# CRUVI.net
KiCad netlist of a schematic drawn in Altium Designer
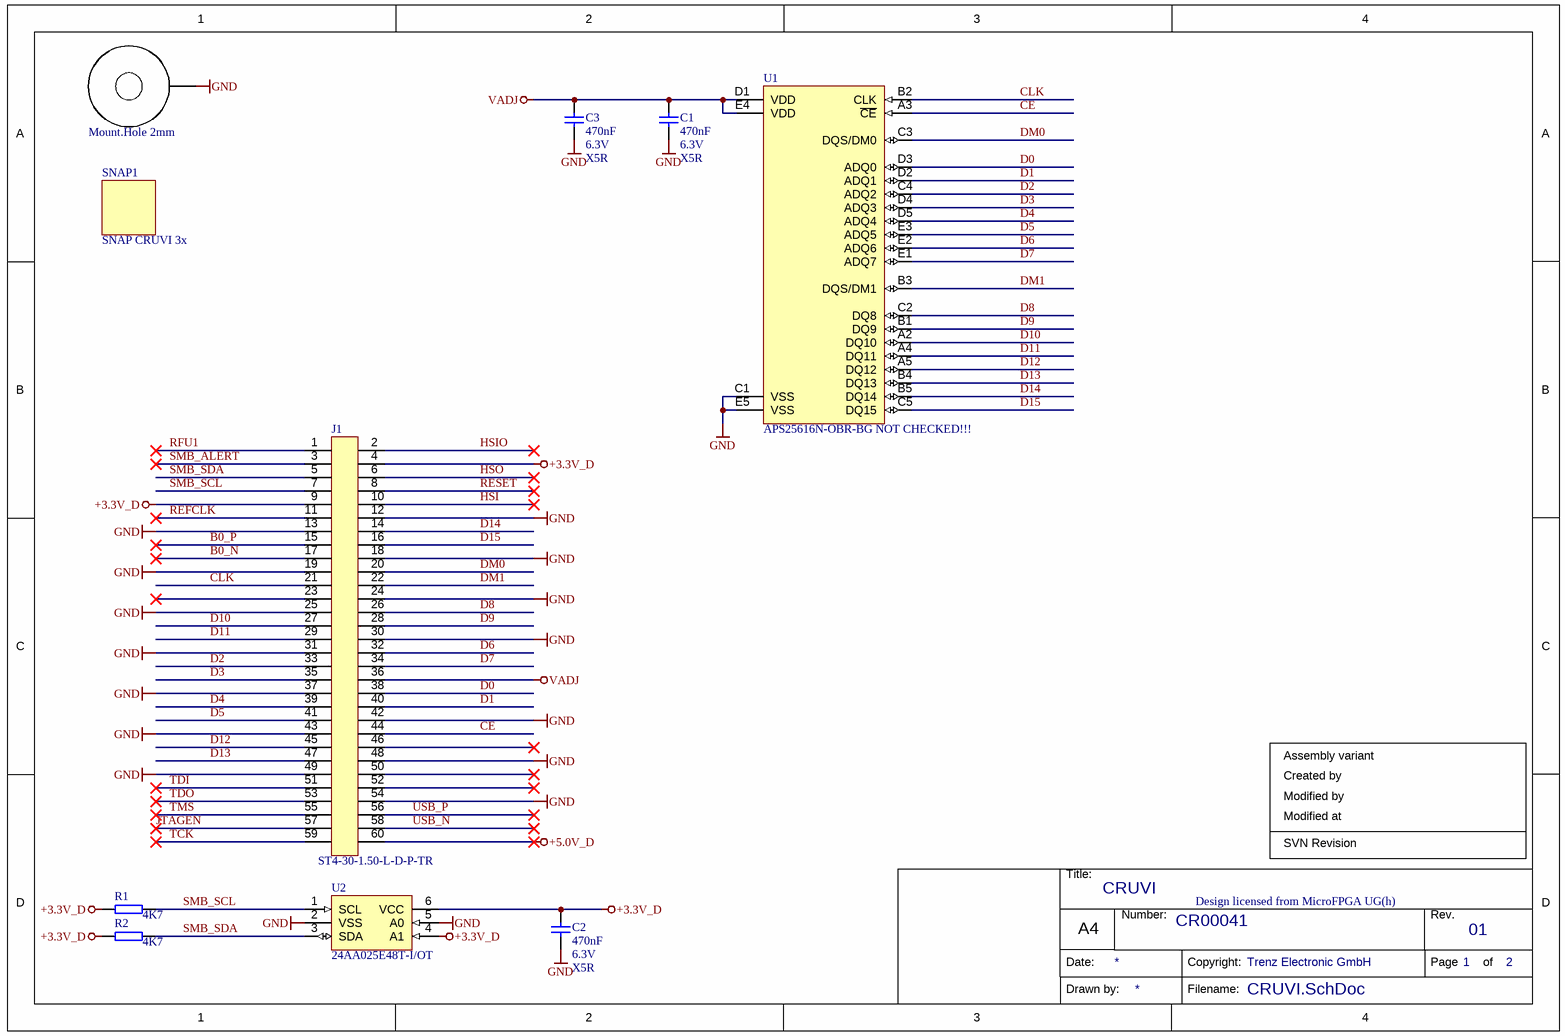
[diagram p0: CRUVI.SchDoc]

(export (version "E")
  (design (tool "Eeschema 10.0.6"))
  (components
    (comp (ref "C1")
      (value "470nF")
      (footprint "CAPC1005X55N_V")
      (description "KON 470nF 6,3V X5R SMD BF 1005 (0402)")
      (fields (field (name "VOLTAGE") "6.3V") (field (name "TECHNOLOGY") "X5R"))
      (libsource (lib "TE") (part "CAP-NP"))
    )
    (comp (ref "C2")
      (value "470nF")
      (footprint "CAPC1005X55N_V")
      (description "KON 470nF 6,3V X5R SMD BF 1005 (0402)")
      (fields (field (name "VOLTAGE") "6.3V") (field (name "TECHNOLOGY") "X5R"))
      (libsource (lib "TE") (part "CAP-NP"))
    )
    (comp (ref "C3")
      (value "470nF")
      (footprint "CAPC1005X55N_V")
      (description "KON 470nF 6,3V X5R SMD BF 1005 (0402)")
      (fields (field (name "VOLTAGE") "6.3V") (field (name "TECHNOLOGY") "X5R"))
      (libsource (lib "TE") (part "CAP-NP"))
    )
    (comp (ref "H3") (value "Mount.Hole 2mm") (footprint "MHole2_2mm") (libsource (lib "TE") (part "MHole")))
    (comp (ref "J1")
      (value "ST4-30-1.50-L-D-P-TR")
      (footprint "ST4-30-1_50-L-D")
      (libsource (lib "TE") (part "CON-60"))
    )
    (comp (ref "R1")
      (value "4K7")
      (footprint "RESC1005X40N_V")
      (description "WID SMD 4K7 1% 0,063W BF 1005 (0402)")
      (fields (field (name "TOLERANCE") "1%"))
      (libsource (lib "TE") (part "RES"))
    )
    (comp (ref "R2")
      (value "4K7")
      (footprint "RESC1005X40N_V")
      (description "WID SMD 4K7 1% 0,063W BF 1005 (0402)")
      (fields (field (name "TOLERANCE") "1%"))
      (libsource (lib "TE") (part "RES"))
    )
    (comp (ref "SNAP1")
      (value "SNAP CRUVI 3x")
      (footprint "CRUVI_3x_Snap")
      (description "SNAP for CRUVI 3x")
      (libsource (lib "TE") (part "DUMMY"))
    )
    (comp (ref "U1")
      (value "APS25616N-OBR-BG NOT CHECKED!!!")
      (footprint "BGA24C100P5X5_800X600X120N")
      (description "APS25616N-OBR-BG")
      (libsource (lib "TE") (part "APS25616N-OBR-BG"))
    )
    (comp (ref "U2")
      (value "24AA025E48T-I/OT")
      (footprint "SOT95P280X145-6N")
      (libsource (lib "TE") (part "24AA025E48"))
    )
  )
  (nets
    (net (code "1") (name "+3.3V_D") (class "Default")
      (node (ref "C2") (pin "1") (pinfunction "1_1") (pintype "passive"))
      (node (ref "J1") (pin "4") (pinfunction "4_4") (pintype "passive"))
      (node (ref "J1") (pin "9") (pinfunction "9_9") (pintype "passive"))
      (node (ref "R1") (pin "1") (pinfunction "1_1") (pintype "passive"))
      (node (ref "R2") (pin "1") (pinfunction "1_1") (pintype "passive"))
      (node (ref "U2") (pin "4") (pinfunction "A1_4") (pintype "input"))
      (node (ref "U2") (pin "6") (pinfunction "VCC_6") (pintype "power_in"))
    )
    (net (code "2") (name "+5.0V_D") (class "Default")
      (node (ref "J1") (pin "60") (pinfunction "60_60") (pintype "passive"))
    )
    (net (code "3") (name "/B0_N") (class "Default")
      (node (ref "J1") (pin "17") (pinfunction "17_17") (pintype "passive+no_connect"))
    )
    (net (code "4") (name "/B0_P") (class "Default")
      (node (ref "J1") (pin "15") (pinfunction "15_15") (pintype "passive+no_connect"))
    )
    (net (code "5") (name "/CE") (class "Default")
      (node (ref "J1") (pin "44") (pinfunction "44_44") (pintype "passive"))
      (node (ref "U1") (pin "A3") (pinfunction "~{CE}_A3") (pintype "input"))
    )
    (net (code "6") (name "/CLK") (class "Default")
      (node (ref "J1") (pin "21") (pinfunction "21_21") (pintype "passive"))
      (node (ref "U1") (pin "B2") (pinfunction "CLK_B2") (pintype "input"))
    )
    (net (code "7") (name "/D0") (class "Default")
      (node (ref "J1") (pin "38") (pinfunction "38_38") (pintype "passive"))
      (node (ref "U1") (pin "D3") (pinfunction "ADQ0_D3") (pintype "bidirectional"))
    )
    (net (code "8") (name "/D1") (class "Default")
      (node (ref "J1") (pin "40") (pinfunction "40_40") (pintype "passive"))
      (node (ref "U1") (pin "D2") (pinfunction "ADQ1_D2") (pintype "bidirectional"))
    )
    (net (code "9") (name "/D2") (class "Default")
      (node (ref "J1") (pin "33") (pinfunction "33_33") (pintype "passive"))
      (node (ref "U1") (pin "C4") (pinfunction "ADQ2_C4") (pintype "bidirectional"))
    )
    (net (code "10") (name "/D3") (class "Default")
      (node (ref "J1") (pin "35") (pinfunction "35_35") (pintype "passive"))
      (node (ref "U1") (pin "D4") (pinfunction "ADQ3_D4") (pintype "bidirectional"))
    )
    (net (code "11") (name "/D4") (class "Default")
      (node (ref "J1") (pin "39") (pinfunction "39_39") (pintype "passive"))
      (node (ref "U1") (pin "D5") (pinfunction "ADQ4_D5") (pintype "bidirectional"))
    )
    (net (code "12") (name "/D5") (class "Default")
      (node (ref "J1") (pin "41") (pinfunction "41_41") (pintype "passive"))
      (node (ref "U1") (pin "E3") (pinfunction "ADQ5_E3") (pintype "bidirectional"))
    )
    (net (code "13") (name "/D6") (class "Default")
      (node (ref "J1") (pin "32") (pinfunction "32_32") (pintype "passive"))
      (node (ref "U1") (pin "E2") (pinfunction "ADQ6_E2") (pintype "bidirectional"))
    )
    (net (code "14") (name "/D7") (class "Default")
      (node (ref "J1") (pin "34") (pinfunction "34_34") (pintype "passive"))
      (node (ref "U1") (pin "E1") (pinfunction "ADQ7_E1") (pintype "bidirectional"))
    )
    (net (code "15") (name "/D8") (class "Default")
      (node (ref "J1") (pin "26") (pinfunction "26_26") (pintype "passive"))
      (node (ref "U1") (pin "C2") (pinfunction "DQ8_C2") (pintype "bidirectional"))
    )
    (net (code "16") (name "/D9") (class "Default")
      (node (ref "J1") (pin "28") (pinfunction "28_28") (pintype "passive"))
      (node (ref "U1") (pin "B1") (pinfunction "DQ9_B1") (pintype "bidirectional"))
    )
    (net (code "17") (name "/D10") (class "Default")
      (node (ref "J1") (pin "27") (pinfunction "27_27") (pintype "passive"))
      (node (ref "U1") (pin "A2") (pinfunction "DQ10_A2") (pintype "bidirectional"))
    )
    (net (code "18") (name "/D11") (class "Default")
      (node (ref "J1") (pin "29") (pinfunction "29_29") (pintype "passive"))
      (node (ref "U1") (pin "A4") (pinfunction "DQ11_A4") (pintype "bidirectional"))
    )
    (net (code "19") (name "/D12") (class "Default")
      (node (ref "J1") (pin "45") (pinfunction "45_45") (pintype "passive"))
      (node (ref "U1") (pin "A5") (pinfunction "DQ12_A5") (pintype "bidirectional"))
    )
    (net (code "20") (name "/D13") (class "Default")
      (node (ref "J1") (pin "47") (pinfunction "47_47") (pintype "passive"))
      (node (ref "U1") (pin "B4") (pinfunction "DQ13_B4") (pintype "bidirectional"))
    )
    (net (code "21") (name "/D14") (class "Default")
      (node (ref "J1") (pin "14") (pinfunction "14_14") (pintype "passive"))
      (node (ref "U1") (pin "B5") (pinfunction "DQ14_B5") (pintype "bidirectional"))
    )
    (net (code "22") (name "/D15") (class "Default")
      (node (ref "J1") (pin "16") (pinfunction "16_16") (pintype "passive"))
      (node (ref "U1") (pin "C5") (pinfunction "DQ15_C5") (pintype "bidirectional"))
    )
    (net (code "23") (name "/DM0") (class "Default")
      (node (ref "J1") (pin "20") (pinfunction "20_20") (pintype "passive"))
      (node (ref "U1") (pin "C3") (pinfunction "DQS/DM0_C3") (pintype "bidirectional"))
    )
    (net (code "24") (name "/DM1") (class "Default")
      (node (ref "J1") (pin "22") (pinfunction "22_22") (pintype "passive"))
      (node (ref "U1") (pin "B3") (pinfunction "DQS/DM1_B3") (pintype "bidirectional"))
    )
    (net (code "25") (name "/HSI") (class "Default")
      (node (ref "J1") (pin "10") (pinfunction "10_10") (pintype "passive+no_connect"))
    )
    (net (code "26") (name "/HSIO") (class "Default")
      (node (ref "J1") (pin "2") (pinfunction "2_2") (pintype "passive+no_connect"))
    )
    (net (code "27") (name "/HSO") (class "Default")
      (node (ref "J1") (pin "6") (pinfunction "6_6") (pintype "passive+no_connect"))
    )
    (net (code "28") (name "/JTAGEN") (class "Default")
      (node (ref "J1") (pin "57") (pinfunction "57_57") (pintype "passive+no_connect"))
    )
    (net (code "29") (name "/REFCLK") (class "Default")
      (node (ref "J1") (pin "11") (pinfunction "11_11") (pintype "passive+no_connect"))
    )
    (net (code "30") (name "/RESET") (class "Default")
      (node (ref "J1") (pin "8") (pinfunction "8_8") (pintype "passive+no_connect"))
    )
    (net (code "31") (name "/RFU1") (class "Default")
      (node (ref "J1") (pin "1") (pinfunction "1_1") (pintype "passive+no_connect"))
    )
    (net (code "32") (name "/SMB_ALERT") (class "Default")
      (node (ref "J1") (pin "3") (pinfunction "3_3") (pintype "passive+no_connect"))
    )
    (net (code "33") (name "/SMB_SCL") (class "Default")
      (node (ref "J1") (pin "7") (pinfunction "7_7") (pintype "passive"))
      (node (ref "R1") (pin "2") (pinfunction "2_2") (pintype "passive"))
      (node (ref "U2") (pin "1") (pinfunction "SCL_1") (pintype "input"))
    )
    (net (code "34") (name "/SMB_SDA") (class "Default")
      (node (ref "J1") (pin "5") (pinfunction "5_5") (pintype "passive"))
      (node (ref "R2") (pin "2") (pinfunction "2_2") (pintype "passive"))
      (node (ref "U2") (pin "3") (pinfunction "SDA_3") (pintype "bidirectional"))
    )
    (net (code "35") (name "/TCK") (class "Default")
      (node (ref "J1") (pin "59") (pinfunction "59_59") (pintype "passive+no_connect"))
    )
    (net (code "36") (name "/TDI") (class "Default")
      (node (ref "J1") (pin "51") (pinfunction "51_51") (pintype "passive+no_connect"))
    )
    (net (code "37") (name "/TDO") (class "Default")
      (node (ref "J1") (pin "53") (pinfunction "53_53") (pintype "passive+no_connect"))
    )
    (net (code "38") (name "/TMS") (class "Default")
      (node (ref "J1") (pin "55") (pinfunction "55_55") (pintype "passive+no_connect"))
    )
    (net (code "39") (name "/USB_N") (class "Default")
      (node (ref "J1") (pin "58") (pinfunction "58_58") (pintype "passive+no_connect"))
    )
    (net (code "40") (name "/USB_P") (class "Default")
      (node (ref "J1") (pin "56") (pinfunction "56_56") (pintype "passive+no_connect"))
    )
    (net (code "41") (name "GND") (class "Default")
      (node (ref "C1") (pin "2") (pinfunction "2_2") (pintype "passive"))
      (node (ref "C2") (pin "2") (pinfunction "2_2") (pintype "passive"))
      (node (ref "C3") (pin "2") (pinfunction "2_2") (pintype "passive"))
      (node (ref "H3") (pin "1") (pinfunction "1_1") (pintype "passive"))
      (node (ref "J1") (pin "12") (pinfunction "12_12") (pintype "passive"))
      (node (ref "J1") (pin "13") (pinfunction "13_13") (pintype "passive"))
      (node (ref "J1") (pin "18") (pinfunction "18_18") (pintype "passive"))
      (node (ref "J1") (pin "19") (pinfunction "19_19") (pintype "passive"))
      (node (ref "J1") (pin "24") (pinfunction "24_24") (pintype "passive"))
      (node (ref "J1") (pin "25") (pinfunction "25_25") (pintype "passive"))
      (node (ref "J1") (pin "30") (pinfunction "30_30") (pintype "passive"))
      (node (ref "J1") (pin "31") (pinfunction "31_31") (pintype "passive"))
      (node (ref "J1") (pin "37") (pinfunction "37_37") (pintype "passive"))
      (node (ref "J1") (pin "42") (pinfunction "42_42") (pintype "passive"))
      (node (ref "J1") (pin "43") (pinfunction "43_43") (pintype "passive"))
      (node (ref "J1") (pin "48") (pinfunction "48_48") (pintype "passive"))
      (node (ref "J1") (pin "49") (pinfunction "49_49") (pintype "passive"))
      (node (ref "J1") (pin "54") (pinfunction "54_54") (pintype "passive"))
      (node (ref "U1") (pin "C1") (pinfunction "VSS_C1") (pintype "power_in"))
      (node (ref "U1") (pin "E5") (pinfunction "VSS_E5") (pintype "power_in"))
      (node (ref "U2") (pin "2") (pinfunction "VSS_2") (pintype "power_in"))
      (node (ref "U2") (pin "5") (pinfunction "A0_5") (pintype "input"))
    )
    (net (code "42") (name "VADJ") (class "Default")
      (node (ref "C1") (pin "1") (pinfunction "1_1") (pintype "passive"))
      (node (ref "C3") (pin "1") (pinfunction "1_1") (pintype "passive"))
      (node (ref "J1") (pin "36") (pinfunction "36_36") (pintype "passive"))
      (node (ref "U1") (pin "D1") (pinfunction "VDD_D1") (pintype "power_in"))
      (node (ref "U1") (pin "E4") (pinfunction "VDD_E4") (pintype "power_in"))
    )
    (net (code "43") (name "unconnected-(J1-Pad23)") (class "Default")
      (node (ref "J1") (pin "23") (pinfunction "23_23") (pintype "passive+no_connect"))
    )
    (net (code "44") (name "unconnected-(J1-Pad46)") (class "Default")
      (node (ref "J1") (pin "46") (pinfunction "46_46") (pintype "passive+no_connect"))
    )
    (net (code "45") (name "unconnected-(J1-Pad50)") (class "Default")
      (node (ref "J1") (pin "50") (pinfunction "50_50") (pintype "passive+no_connect"))
    )
    (net (code "46") (name "unconnected-(J1-Pad52)") (class "Default")
      (node (ref "J1") (pin "52") (pinfunction "52_52") (pintype "passive+no_connect"))
    )
  )
)
